# tester-2.net
KiCad netlist of a schematic drawn in EAGLE
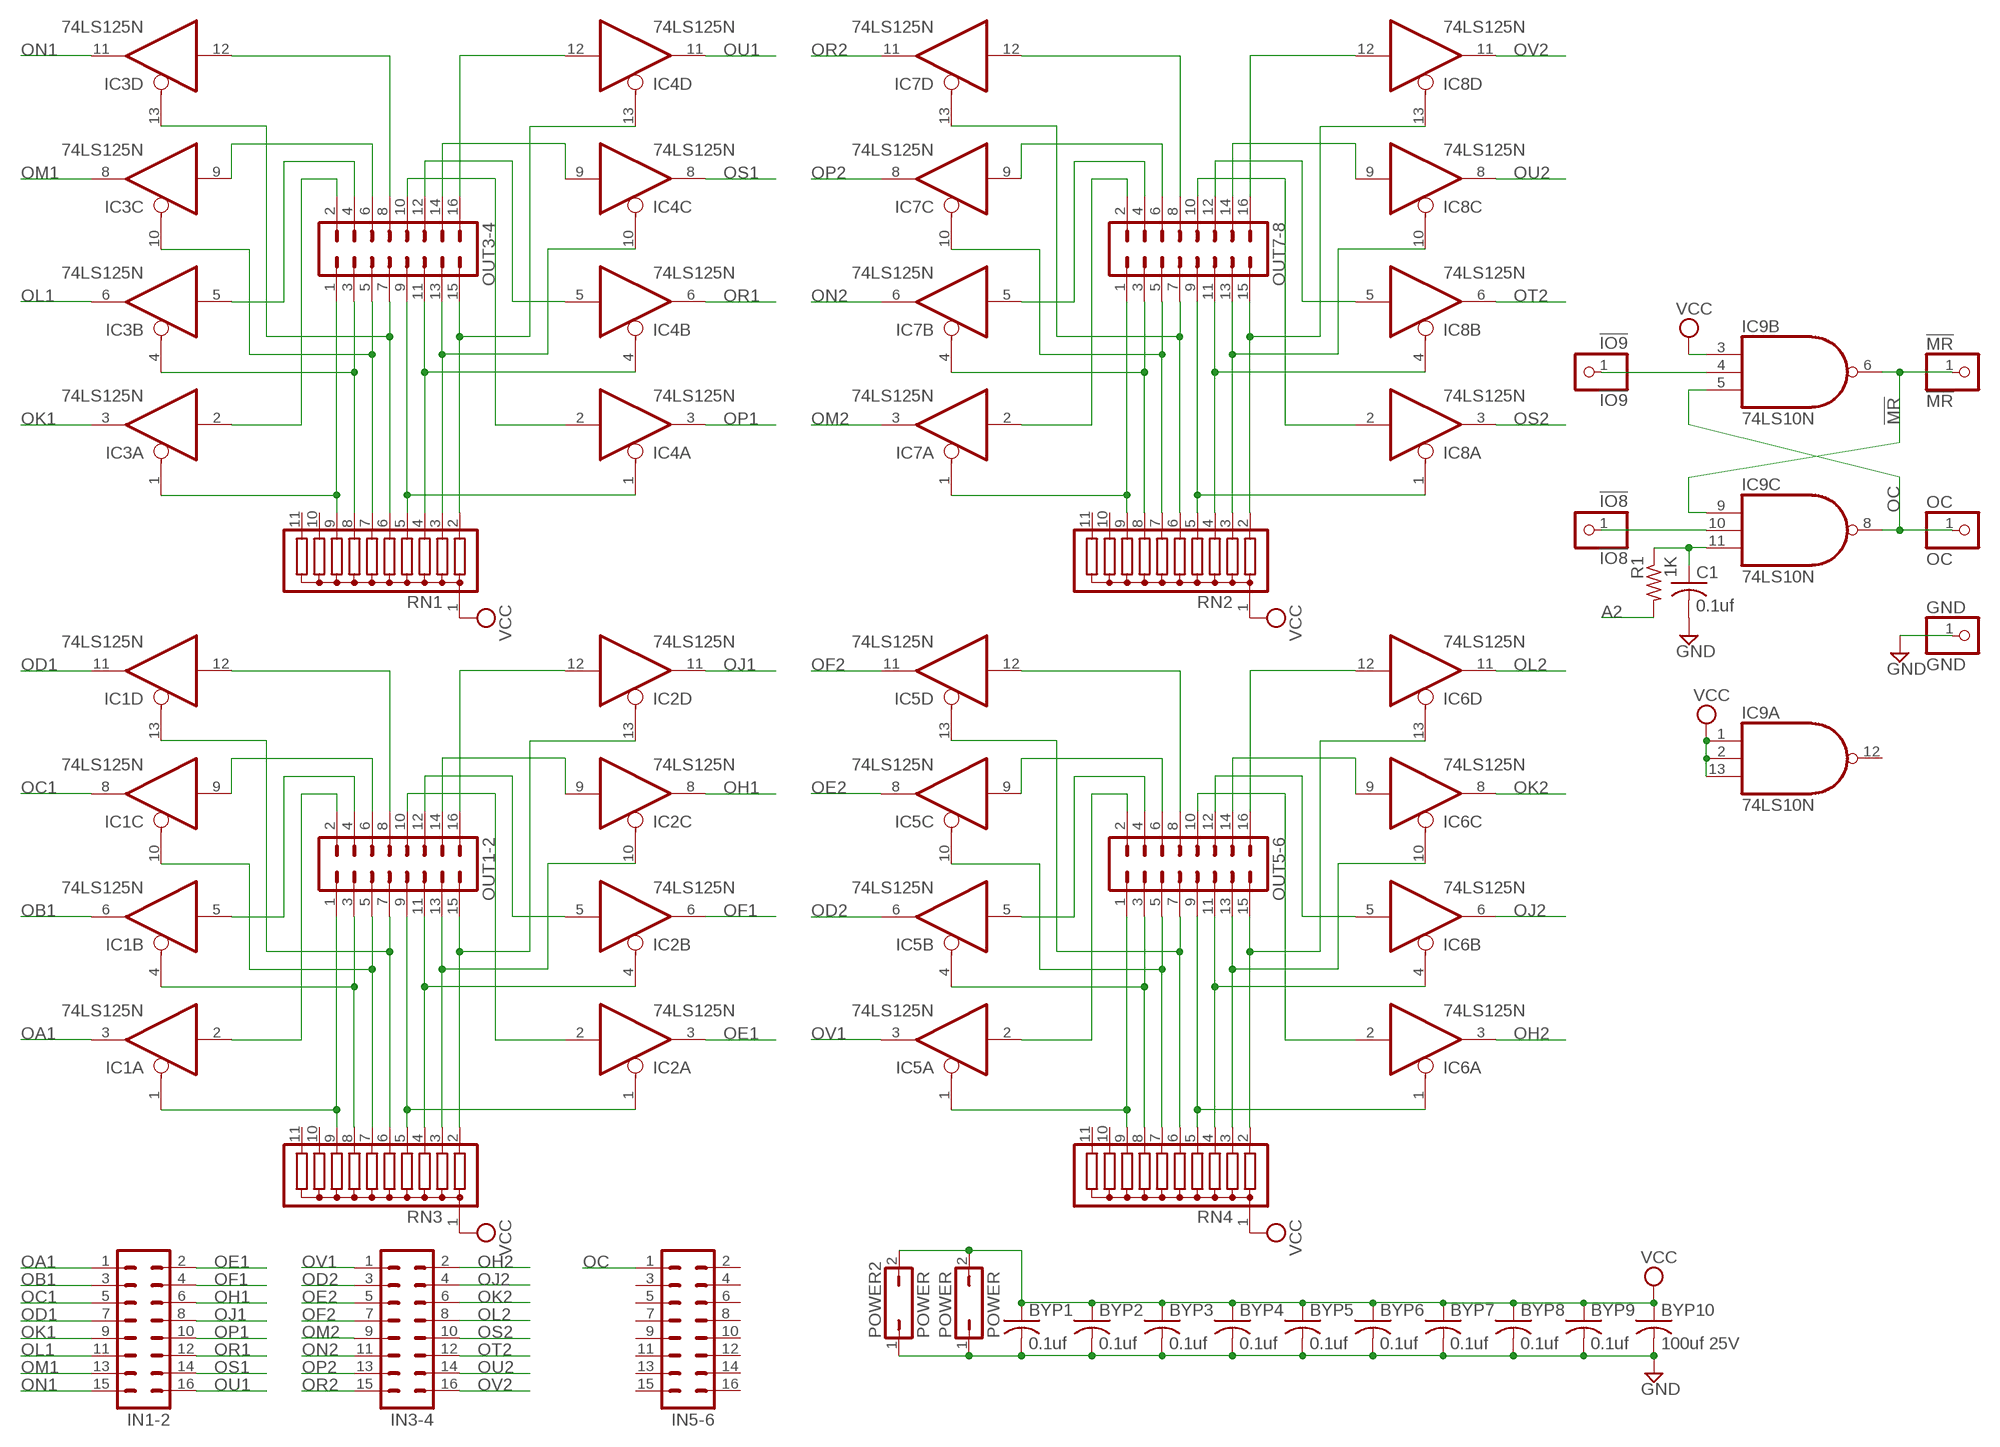
[diagram p0: schematic, sheet 1]
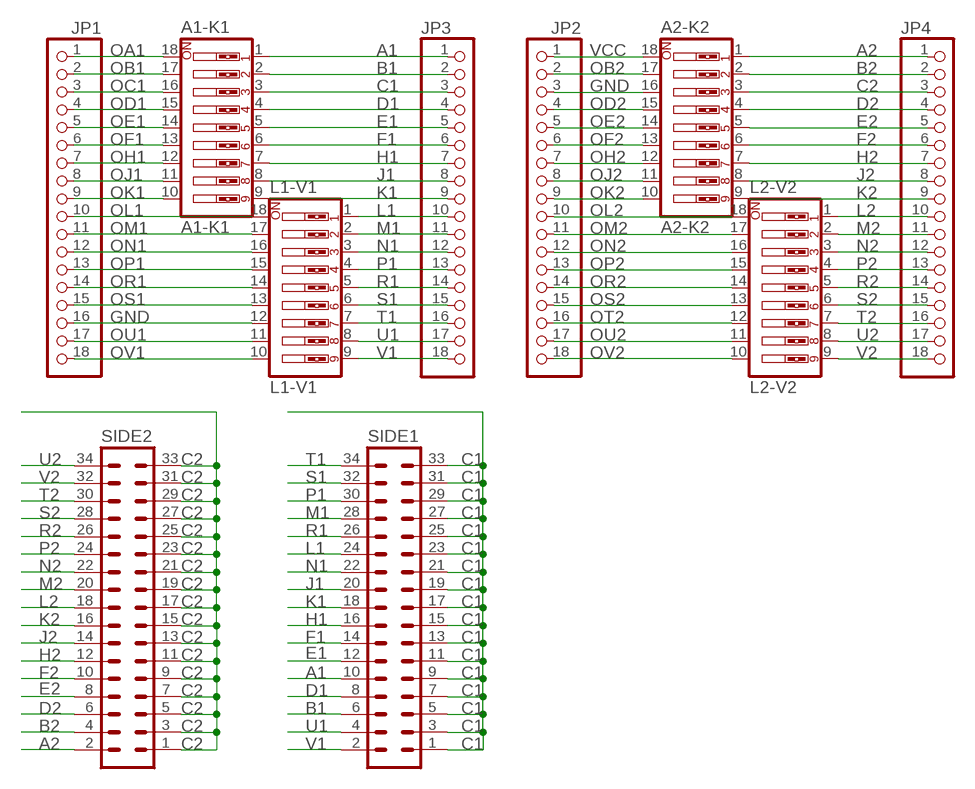
[diagram p1: schematic, sheet 2]

(export (version "E")
  (design (tool "Eeschema 10.0.6"))
  (components
    (comp (ref "A1-K1")
      (value "A1-K1")
      (footprint "eagle-import:EDG-09")
      (libsource (lib "eagle-import") (part "SW_DIP-9"))
    )
    (comp (ref "A2-K2")
      (value "A2-K2")
      (footprint "eagle-import:EDG-09")
      (libsource (lib "eagle-import") (part "SW_DIP-9"))
    )
    (comp (ref "JP1")
      (value "PINHD-1X18")
      (footprint "eagle-import:1X18")
      (libsource (lib "eagle-import") (part "PINHD-1X18"))
    )
    (comp (ref "JP2")
      (value "PINHD-1X18")
      (footprint "eagle-import:1X18")
      (libsource (lib "eagle-import") (part "PINHD-1X18"))
    )
    (comp (ref "JP3")
      (value "PINHD-1X18")
      (footprint "eagle-import:1X18")
      (libsource (lib "eagle-import") (part "PINHD-1X18"))
    )
    (comp (ref "JP4")
      (value "PINHD-1X18")
      (footprint "eagle-import:1X18")
      (libsource (lib "eagle-import") (part "PINHD-1X18"))
    )
    (comp (ref "L1-V1")
      (value "L1-V1")
      (footprint "eagle-import:EDG-09")
      (libsource (lib "eagle-import") (part "SW_DIP-9"))
    )
    (comp (ref "L2-V2")
      (value "L2-V2")
      (footprint "eagle-import:EDG-09")
      (libsource (lib "eagle-import") (part "SW_DIP-9"))
    )
    (comp (ref "SIDE1")
      (value "MA17-2")
      (footprint "eagle-import:MA17-2")
      (libsource (lib "eagle-import") (part "MA17-2"))
    )
    (comp (ref "SIDE2")
      (value "MA17-2")
      (footprint "eagle-import:MA17-2")
      (libsource (lib "eagle-import") (part "MA17-2"))
    )
    (comp (ref "!IO8")
      (value "!IO8")
      (footprint "eagle-import:1X01")
      (libsource (lib "eagle-import") (part "PINHD-1X1"))
    )
    (comp (ref "!IO9")
      (value "!IO9")
      (footprint "eagle-import:1X01")
      (libsource (lib "eagle-import") (part "PINHD-1X1"))
    )
    (comp (ref "!MR")
      (value "!MR")
      (footprint "eagle-import:1X01")
      (libsource (lib "eagle-import") (part "PINHD-1X1"))
    )
    (comp (ref "BYP1")
      (value "0.1uf")
      (footprint "eagle-import:C050-025X075")
      (libsource (lib "eagle-import") (part "C-US050-025X075"))
    )
    (comp (ref "BYP2")
      (value "0.1uf")
      (footprint "eagle-import:C050-025X075")
      (libsource (lib "eagle-import") (part "C-US050-025X075"))
    )
    (comp (ref "BYP3")
      (value "0.1uf")
      (footprint "eagle-import:C050-025X075")
      (libsource (lib "eagle-import") (part "C-US050-025X075"))
    )
    (comp (ref "BYP4")
      (value "0.1uf")
      (footprint "eagle-import:C050-025X075")
      (libsource (lib "eagle-import") (part "C-US050-025X075"))
    )
    (comp (ref "BYP5")
      (value "0.1uf")
      (footprint "eagle-import:C050-025X075")
      (libsource (lib "eagle-import") (part "C-US050-025X075"))
    )
    (comp (ref "BYP6")
      (value "0.1uf")
      (footprint "eagle-import:C050-025X075")
      (libsource (lib "eagle-import") (part "C-US050-025X075"))
    )
    (comp (ref "BYP7")
      (value "0.1uf")
      (footprint "eagle-import:C050-025X075")
      (libsource (lib "eagle-import") (part "C-US050-025X075"))
    )
    (comp (ref "BYP8")
      (value "0.1uf")
      (footprint "eagle-import:C050-025X075")
      (libsource (lib "eagle-import") (part "C-US050-025X075"))
    )
    (comp (ref "BYP9")
      (value "0.1uf")
      (footprint "eagle-import:C050-025X075")
      (libsource (lib "eagle-import") (part "C-US050-025X075"))
    )
    (comp (ref "BYP10")
      (value "100uf 25V")
      (footprint "eagle-import:C150-064X183")
      (libsource (lib "eagle-import") (part "C-US150-064X183"))
    )
    (comp (ref "C1")
      (value "0.1uf")
      (footprint "eagle-import:C050-025X075")
      (libsource (lib "eagle-import") (part "C-US050-025X075"))
    )
    (comp (ref "GND")
      (value "GND")
      (footprint "eagle-import:1X01")
      (libsource (lib "eagle-import") (part "PINHD-1X1"))
    )
    (comp (ref "IC1")
      (value "74LS125N")
      (footprint "eagle-import:DIL14")
      (libsource (lib "eagle-import") (part "74125NLS"))
    )
    (comp (ref "IC2")
      (value "74LS125N")
      (footprint "eagle-import:DIL14")
      (libsource (lib "eagle-import") (part "74125NLS"))
    )
    (comp (ref "IC3")
      (value "74LS125N")
      (footprint "eagle-import:DIL14")
      (libsource (lib "eagle-import") (part "74125NLS"))
    )
    (comp (ref "IC4")
      (value "74LS125N")
      (footprint "eagle-import:DIL14")
      (libsource (lib "eagle-import") (part "74125NLS"))
    )
    (comp (ref "IC5")
      (value "74LS125N")
      (footprint "eagle-import:DIL14")
      (libsource (lib "eagle-import") (part "74125NLS"))
    )
    (comp (ref "IC6")
      (value "74LS125N")
      (footprint "eagle-import:DIL14")
      (libsource (lib "eagle-import") (part "74125NLS"))
    )
    (comp (ref "IC7")
      (value "74LS125N")
      (footprint "eagle-import:DIL14")
      (libsource (lib "eagle-import") (part "74125NLS"))
    )
    (comp (ref "IC8")
      (value "74LS125N")
      (footprint "eagle-import:DIL14")
      (libsource (lib "eagle-import") (part "74125NLS"))
    )
    (comp (ref "IC9")
      (value "74LS10N")
      (footprint "eagle-import:DIL14")
      (libsource (lib "eagle-import") (part "7410NLS"))
    )
    (comp (ref "IN1-2")
      (value "MA08-2")
      (footprint "eagle-import:MA08-2")
      (libsource (lib "eagle-import") (part "MA08-2"))
    )
    (comp (ref "IN3-4")
      (value "MA08-2")
      (footprint "eagle-import:MA08-2")
      (libsource (lib "eagle-import") (part "MA08-2"))
    )
    (comp (ref "IN5-6")
      (value "MA08-2")
      (footprint "eagle-import:MA08-2")
      (libsource (lib "eagle-import") (part "MA08-2"))
    )
    (comp (ref "OC")
      (value "OC")
      (footprint "eagle-import:1X01")
      (libsource (lib "eagle-import") (part "PINHD-1X1"))
    )
    (comp (ref "OUT1-2")
      (value "MA08-2")
      (footprint "eagle-import:MA08-2")
      (libsource (lib "eagle-import") (part "MA08-2"))
    )
    (comp (ref "OUT3-4")
      (value "MA08-2")
      (footprint "eagle-import:MA08-2")
      (libsource (lib "eagle-import") (part "MA08-2"))
    )
    (comp (ref "OUT5-6")
      (value "MA08-2")
      (footprint "eagle-import:MA08-2")
      (libsource (lib "eagle-import") (part "MA08-2"))
    )
    (comp (ref "OUT7-8")
      (value "MA08-2")
      (footprint "eagle-import:MA08-2")
      (libsource (lib "eagle-import") (part "MA08-2"))
    )
    (comp (ref "POWER")
      (value "POWER")
      (footprint "eagle-import:JP1")
      (libsource (lib "eagle-import") (part "JP1Q"))
    )
    (comp (ref "POWER2")
      (value "POWER")
      (footprint "eagle-import:JP1")
      (libsource (lib "eagle-import") (part "JP1Q"))
    )
    (comp (ref "R1")
      (value "1K")
      (footprint "eagle-import:0207_10")
      (libsource (lib "eagle-import") (part "R-US_0207/10"))
    )
    (comp (ref "RN1")
      (value "G10R")
      (footprint "eagle-import:SIL11")
      (libsource (lib "eagle-import") (part "G10R"))
    )
    (comp (ref "RN2")
      (value "G10R")
      (footprint "eagle-import:SIL11")
      (libsource (lib "eagle-import") (part "G10R"))
    )
    (comp (ref "RN3")
      (value "G10R")
      (footprint "eagle-import:SIL11")
      (libsource (lib "eagle-import") (part "G10R"))
    )
    (comp (ref "RN4")
      (value "G10R")
      (footprint "eagle-import:SIL11")
      (libsource (lib "eagle-import") (part "G10R"))
    )
  )
  (nets
    (net (code "1") (name "A1") (class "Default")
      (node (ref "A1-K1") (pin "1") (pinfunction "1_1") (pintype "passive"))
      (node (ref "JP3") (pin "1") (pinfunction "1_1") (pintype "passive"))
      (node (ref "SIDE1") (pin "10") (pinfunction "10_10") (pintype "passive"))
    )
    (net (code "2") (name "A2") (class "Default")
      (node (ref "A2-K2") (pin "1") (pinfunction "1_1") (pintype "passive"))
      (node (ref "JP4") (pin "1") (pinfunction "1_1") (pintype "passive"))
      (node (ref "R1") (pin "2") (pinfunction "2_2") (pintype "passive"))
      (node (ref "SIDE2") (pin "2") (pinfunction "2_2") (pintype "passive"))
    )
    (net (code "3") (name "B1") (class "Default")
      (node (ref "A1-K1") (pin "2") (pinfunction "2_2") (pintype "passive"))
      (node (ref "JP3") (pin "2") (pinfunction "2_2") (pintype "passive"))
      (node (ref "SIDE1") (pin "6") (pinfunction "6_6") (pintype "passive"))
    )
    (net (code "4") (name "B2") (class "Default")
      (node (ref "A2-K2") (pin "2") (pinfunction "2_2") (pintype "passive"))
      (node (ref "JP4") (pin "2") (pinfunction "2_2") (pintype "passive"))
      (node (ref "SIDE2") (pin "4") (pinfunction "4_4") (pintype "passive"))
    )
    (net (code "5") (name "C1") (class "Default")
      (node (ref "A1-K1") (pin "3") (pinfunction "3_3") (pintype "passive"))
      (node (ref "JP3") (pin "3") (pinfunction "3_3") (pintype "passive"))
      (node (ref "SIDE1") (pin "1") (pinfunction "1_1") (pintype "passive"))
      (node (ref "SIDE1") (pin "11") (pinfunction "11_11") (pintype "passive"))
      (node (ref "SIDE1") (pin "13") (pinfunction "13_13") (pintype "passive"))
      (node (ref "SIDE1") (pin "15") (pinfunction "15_15") (pintype "passive"))
      (node (ref "SIDE1") (pin "17") (pinfunction "17_17") (pintype "passive"))
      (node (ref "SIDE1") (pin "19") (pinfunction "19_19") (pintype "passive"))
      (node (ref "SIDE1") (pin "21") (pinfunction "21_21") (pintype "passive"))
      (node (ref "SIDE1") (pin "23") (pinfunction "23_23") (pintype "passive"))
      (node (ref "SIDE1") (pin "25") (pinfunction "25_25") (pintype "passive"))
      (node (ref "SIDE1") (pin "27") (pinfunction "27_27") (pintype "passive"))
      (node (ref "SIDE1") (pin "29") (pinfunction "29_29") (pintype "passive"))
      (node (ref "SIDE1") (pin "3") (pinfunction "3_3") (pintype "passive"))
      (node (ref "SIDE1") (pin "31") (pinfunction "31_31") (pintype "passive"))
      (node (ref "SIDE1") (pin "33") (pinfunction "33_33") (pintype "passive"))
      (node (ref "SIDE1") (pin "5") (pinfunction "5_5") (pintype "passive"))
      (node (ref "SIDE1") (pin "7") (pinfunction "7_7") (pintype "passive"))
      (node (ref "SIDE1") (pin "9") (pinfunction "9_9") (pintype "passive"))
    )
    (net (code "6") (name "C2") (class "Default")
      (node (ref "A2-K2") (pin "3") (pinfunction "3_3") (pintype "passive"))
      (node (ref "JP4") (pin "3") (pinfunction "3_3") (pintype "passive"))
      (node (ref "SIDE2") (pin "1") (pinfunction "1_1") (pintype "passive"))
      (node (ref "SIDE2") (pin "11") (pinfunction "11_11") (pintype "passive"))
      (node (ref "SIDE2") (pin "13") (pinfunction "13_13") (pintype "passive"))
      (node (ref "SIDE2") (pin "15") (pinfunction "15_15") (pintype "passive"))
      (node (ref "SIDE2") (pin "17") (pinfunction "17_17") (pintype "passive"))
      (node (ref "SIDE2") (pin "19") (pinfunction "19_19") (pintype "passive"))
      (node (ref "SIDE2") (pin "21") (pinfunction "21_21") (pintype "passive"))
      (node (ref "SIDE2") (pin "23") (pinfunction "23_23") (pintype "passive"))
      (node (ref "SIDE2") (pin "25") (pinfunction "25_25") (pintype "passive"))
      (node (ref "SIDE2") (pin "27") (pinfunction "27_27") (pintype "passive"))
      (node (ref "SIDE2") (pin "29") (pinfunction "29_29") (pintype "passive"))
      (node (ref "SIDE2") (pin "3") (pinfunction "3_3") (pintype "passive"))
      (node (ref "SIDE2") (pin "31") (pinfunction "31_31") (pintype "passive"))
      (node (ref "SIDE2") (pin "33") (pinfunction "33_33") (pintype "passive"))
      (node (ref "SIDE2") (pin "5") (pinfunction "5_5") (pintype "passive"))
      (node (ref "SIDE2") (pin "7") (pinfunction "7_7") (pintype "passive"))
      (node (ref "SIDE2") (pin "9") (pinfunction "9_9") (pintype "passive"))
    )
    (net (code "7") (name "D1") (class "Default")
      (node (ref "A1-K1") (pin "4") (pinfunction "4_4") (pintype "passive"))
      (node (ref "JP3") (pin "4") (pinfunction "4_4") (pintype "passive"))
      (node (ref "SIDE1") (pin "8") (pinfunction "8_8") (pintype "passive"))
    )
    (net (code "8") (name "D2") (class "Default")
      (node (ref "A2-K2") (pin "4") (pinfunction "4_4") (pintype "passive"))
      (node (ref "JP4") (pin "4") (pinfunction "4_4") (pintype "passive"))
      (node (ref "SIDE2") (pin "6") (pinfunction "6_6") (pintype "passive"))
    )
    (net (code "9") (name "E1") (class "Default")
      (node (ref "A1-K1") (pin "5") (pinfunction "5_5") (pintype "passive"))
      (node (ref "JP3") (pin "5") (pinfunction "5_5") (pintype "passive"))
      (node (ref "SIDE1") (pin "12") (pinfunction "12_12") (pintype "passive"))
    )
    (net (code "10") (name "E2") (class "Default")
      (node (ref "A2-K2") (pin "5") (pinfunction "5_5") (pintype "passive"))
      (node (ref "JP4") (pin "5") (pinfunction "5_5") (pintype "passive"))
      (node (ref "SIDE2") (pin "8") (pinfunction "8_8") (pintype "passive"))
    )
    (net (code "11") (name "F1") (class "Default")
      (node (ref "A1-K1") (pin "6") (pinfunction "6_6") (pintype "passive"))
      (node (ref "JP3") (pin "6") (pinfunction "6_6") (pintype "passive"))
      (node (ref "SIDE1") (pin "14") (pinfunction "14_14") (pintype "passive"))
    )
    (net (code "12") (name "F2") (class "Default")
      (node (ref "A2-K2") (pin "6") (pinfunction "6_6") (pintype "passive"))
      (node (ref "JP4") (pin "6") (pinfunction "6_6") (pintype "passive"))
      (node (ref "SIDE2") (pin "10") (pinfunction "10_10") (pintype "passive"))
    )
    (net (code "13") (name "GND") (class "Default")
      (node (ref "A2-K2") (pin "16") (pinfunction "16_16") (pintype "passive"))
      (node (ref "BYP1") (pin "2") (pinfunction "2_2") (pintype "passive"))
      (node (ref "BYP10") (pin "2") (pinfunction "2_2") (pintype "passive"))
      (node (ref "BYP2") (pin "2") (pinfunction "2_2") (pintype "passive"))
      (node (ref "BYP3") (pin "2") (pinfunction "2_2") (pintype "passive"))
      (node (ref "BYP4") (pin "2") (pinfunction "2_2") (pintype "passive"))
      (node (ref "BYP5") (pin "2") (pinfunction "2_2") (pintype "passive"))
      (node (ref "BYP6") (pin "2") (pinfunction "2_2") (pintype "passive"))
      (node (ref "BYP7") (pin "2") (pinfunction "2_2") (pintype "passive"))
      (node (ref "BYP8") (pin "2") (pinfunction "2_2") (pintype "passive"))
      (node (ref "BYP9") (pin "2") (pinfunction "2_2") (pintype "passive"))
      (node (ref "C1") (pin "2") (pinfunction "2_2") (pintype "passive"))
      (node (ref "GND") (pin "1") (pinfunction "1_1") (pintype "passive"))
      (node (ref "JP1") (pin "16") (pinfunction "16_16") (pintype "passive"))
      (node (ref "JP2") (pin "3") (pinfunction "3_3") (pintype "passive"))
      (node (ref "L1-V1") (pin "12") (pinfunction "12_12") (pintype "passive"))
      (node (ref "POWER") (pin "1") (pinfunction "1_1") (pintype "passive"))
      (node (ref "POWER2") (pin "1") (pinfunction "1_1") (pintype "passive"))
    )
    (net (code "14") (name "H1") (class "Default")
      (node (ref "A1-K1") (pin "7") (pinfunction "7_7") (pintype "passive"))
      (node (ref "JP3") (pin "7") (pinfunction "7_7") (pintype "passive"))
      (node (ref "SIDE1") (pin "16") (pinfunction "16_16") (pintype "passive"))
    )
    (net (code "15") (name "H2") (class "Default")
      (node (ref "A2-K2") (pin "7") (pinfunction "7_7") (pintype "passive"))
      (node (ref "JP4") (pin "7") (pinfunction "7_7") (pintype "passive"))
      (node (ref "SIDE2") (pin "12") (pinfunction "12_12") (pintype "passive"))
    )
    (net (code "16") (name "J1") (class "Default")
      (node (ref "A1-K1") (pin "8") (pinfunction "8_8") (pintype "passive"))
      (node (ref "JP3") (pin "8") (pinfunction "8_8") (pintype "passive"))
      (node (ref "SIDE1") (pin "20") (pinfunction "20_20") (pintype "passive"))
    )
    (net (code "17") (name "J2") (class "Default")
      (node (ref "A2-K2") (pin "8") (pinfunction "8_8") (pintype "passive"))
      (node (ref "JP4") (pin "8") (pinfunction "8_8") (pintype "passive"))
      (node (ref "SIDE2") (pin "14") (pinfunction "14_14") (pintype "passive"))
    )
    (net (code "18") (name "K1") (class "Default")
      (node (ref "A1-K1") (pin "9") (pinfunction "9_9") (pintype "passive"))
      (node (ref "JP3") (pin "9") (pinfunction "9_9") (pintype "passive"))
      (node (ref "SIDE1") (pin "18") (pinfunction "18_18") (pintype "passive"))
    )
    (net (code "19") (name "K2") (class "Default")
      (node (ref "A2-K2") (pin "9") (pinfunction "9_9") (pintype "passive"))
      (node (ref "JP4") (pin "9") (pinfunction "9_9") (pintype "passive"))
      (node (ref "SIDE2") (pin "16") (pinfunction "16_16") (pintype "passive"))
    )
    (net (code "20") (name "L1") (class "Default")
      (node (ref "JP3") (pin "10") (pinfunction "10_10") (pintype "passive"))
      (node (ref "L1-V1") (pin "1") (pinfunction "1_1") (pintype "passive"))
      (node (ref "SIDE1") (pin "24") (pinfunction "24_24") (pintype "passive"))
    )
    (net (code "21") (name "L2") (class "Default")
      (node (ref "JP4") (pin "10") (pinfunction "10_10") (pintype "passive"))
      (node (ref "L2-V2") (pin "1") (pinfunction "1_1") (pintype "passive"))
      (node (ref "SIDE2") (pin "18") (pinfunction "18_18") (pintype "passive"))
    )
    (net (code "22") (name "M1") (class "Default")
      (node (ref "JP3") (pin "11") (pinfunction "11_11") (pintype "passive"))
      (node (ref "L1-V1") (pin "2") (pinfunction "2_2") (pintype "passive"))
      (node (ref "SIDE1") (pin "28") (pinfunction "28_28") (pintype "passive"))
    )
    (net (code "23") (name "M2") (class "Default")
      (node (ref "JP4") (pin "11") (pinfunction "11_11") (pintype "passive"))
      (node (ref "L2-V2") (pin "2") (pinfunction "2_2") (pintype "passive"))
      (node (ref "SIDE2") (pin "20") (pinfunction "20_20") (pintype "passive"))
    )
    (net (code "24") (name "N1") (class "Default")
      (node (ref "JP3") (pin "12") (pinfunction "12_12") (pintype "passive"))
      (node (ref "L1-V1") (pin "3") (pinfunction "3_3") (pintype "passive"))
      (node (ref "SIDE1") (pin "22") (pinfunction "22_22") (pintype "passive"))
    )
    (net (code "25") (name "N2") (class "Default")
      (node (ref "JP4") (pin "12") (pinfunction "12_12") (pintype "passive"))
      (node (ref "L2-V2") (pin "3") (pinfunction "3_3") (pintype "passive"))
      (node (ref "SIDE2") (pin "22") (pinfunction "22_22") (pintype "passive"))
    )
    (net (code "26") (name "Net-(IC1A-I)") (class "Default")
      (node (ref "IC1") (pin "2") (pinfunction "I_2") (pintype "input"))
      (node (ref "OUT1-2") (pin "2") (pinfunction "2_2") (pintype "passive"))
    )
    (net (code "27") (name "Net-(IC1A-OE)") (class "Default")
      (node (ref "IC1") (pin "1") (pinfunction "OE_1") (pintype "input"))
      (node (ref "OUT1-2") (pin "1") (pinfunction "1_1") (pintype "passive"))
      (node (ref "RN3") (pin "9") (pinfunction "9_9") (pintype "passive"))
    )
    (net (code "28") (name "Net-(IC1B-I)") (class "Default")
      (node (ref "IC1") (pin "5") (pinfunction "I_5") (pintype "input"))
      (node (ref "OUT1-2") (pin "4") (pinfunction "4_4") (pintype "passive"))
    )
    (net (code "29") (name "Net-(IC1B-OE)") (class "Default")
      (node (ref "IC1") (pin "4") (pinfunction "OE_4") (pintype "input"))
      (node (ref "OUT1-2") (pin "3") (pinfunction "3_3") (pintype "passive"))
      (node (ref "RN3") (pin "8") (pinfunction "8_8") (pintype "passive"))
    )
    (net (code "30") (name "Net-(IC1C-I)") (class "Default")
      (node (ref "IC1") (pin "9") (pinfunction "I_9") (pintype "input"))
      (node (ref "OUT1-2") (pin "6") (pinfunction "6_6") (pintype "passive"))
    )
    (net (code "31") (name "Net-(IC1C-OE)") (class "Default")
      (node (ref "IC1") (pin "10") (pinfunction "OE_10") (pintype "input"))
      (node (ref "OUT1-2") (pin "5") (pinfunction "5_5") (pintype "passive"))
      (node (ref "RN3") (pin "7") (pinfunction "7_7") (pintype "passive"))
    )
    (net (code "32") (name "Net-(IC1D-I)") (class "Default")
      (node (ref "IC1") (pin "12") (pinfunction "I_12") (pintype "input"))
      (node (ref "OUT1-2") (pin "8") (pinfunction "8_8") (pintype "passive"))
    )
    (net (code "33") (name "Net-(IC1D-OE)") (class "Default")
      (node (ref "IC1") (pin "13") (pinfunction "OE_13") (pintype "input"))
      (node (ref "OUT1-2") (pin "7") (pinfunction "7_7") (pintype "passive"))
      (node (ref "RN3") (pin "6") (pinfunction "6_6") (pintype "passive"))
    )
    (net (code "34") (name "Net-(IC2A-I)") (class "Default")
      (node (ref "IC2") (pin "2") (pinfunction "I_2") (pintype "input"))
      (node (ref "OUT1-2") (pin "10") (pinfunction "10_10") (pintype "passive"))
    )
    (net (code "35") (name "Net-(IC2A-OE)") (class "Default")
      (node (ref "IC2") (pin "1") (pinfunction "OE_1") (pintype "input"))
      (node (ref "OUT1-2") (pin "9") (pinfunction "9_9") (pintype "passive"))
      (node (ref "RN3") (pin "5") (pinfunction "5_5") (pintype "passive"))
    )
    (net (code "36") (name "Net-(IC2B-I)") (class "Default")
      (node (ref "IC2") (pin "5") (pinfunction "I_5") (pintype "input"))
      (node (ref "OUT1-2") (pin "12") (pinfunction "12_12") (pintype "passive"))
    )
    (net (code "37") (name "Net-(IC2B-OE)") (class "Default")
      (node (ref "IC2") (pin "4") (pinfunction "OE_4") (pintype "input"))
      (node (ref "OUT1-2") (pin "11") (pinfunction "11_11") (pintype "passive"))
      (node (ref "RN3") (pin "4") (pinfunction "4_4") (pintype "passive"))
    )
    (net (code "38") (name "Net-(IC2C-I)") (class "Default")
      (node (ref "IC2") (pin "9") (pinfunction "I_9") (pintype "input"))
      (node (ref "OUT1-2") (pin "14") (pinfunction "14_14") (pintype "passive"))
    )
    (net (code "39") (name "Net-(IC2C-OE)") (class "Default")
      (node (ref "IC2") (pin "10") (pinfunction "OE_10") (pintype "input"))
      (node (ref "OUT1-2") (pin "13") (pinfunction "13_13") (pintype "passive"))
      (node (ref "RN3") (pin "3") (pinfunction "3_3") (pintype "passive"))
    )
    (net (code "40") (name "Net-(IC2D-I)") (class "Default")
      (node (ref "IC2") (pin "12") (pinfunction "I_12") (pintype "input"))
      (node (ref "OUT1-2") (pin "16") (pinfunction "16_16") (pintype "passive"))
    )
    (net (code "41") (name "Net-(IC2D-OE)") (class "Default")
      (node (ref "IC2") (pin "13") (pinfunction "OE_13") (pintype "input"))
      (node (ref "OUT1-2") (pin "15") (pinfunction "15_15") (pintype "passive"))
      (node (ref "RN3") (pin "2") (pinfunction "2_2") (pintype "passive"))
    )
    (net (code "42") (name "Net-(IC3A-I)") (class "Default")
      (node (ref "IC3") (pin "2") (pinfunction "I_2") (pintype "input"))
      (node (ref "OUT3-4") (pin "2") (pinfunction "2_2") (pintype "passive"))
    )
    (net (code "43") (name "Net-(IC3A-OE)") (class "Default")
      (node (ref "IC3") (pin "1") (pinfunction "OE_1") (pintype "input"))
      (node (ref "OUT3-4") (pin "1") (pinfunction "1_1") (pintype "passive"))
      (node (ref "RN1") (pin "9") (pinfunction "9_9") (pintype "passive"))
    )
    (net (code "44") (name "Net-(IC3B-I)") (class "Default")
      (node (ref "IC3") (pin "5") (pinfunction "I_5") (pintype "input"))
      (node (ref "OUT3-4") (pin "4") (pinfunction "4_4") (pintype "passive"))
    )
    (net (code "45") (name "Net-(IC3B-OE)") (class "Default")
      (node (ref "IC3") (pin "4") (pinfunction "OE_4") (pintype "input"))
      (node (ref "OUT3-4") (pin "3") (pinfunction "3_3") (pintype "passive"))
      (node (ref "RN1") (pin "8") (pinfunction "8_8") (pintype "passive"))
    )
    (net (code "46") (name "Net-(IC3C-I)") (class "Default")
      (node (ref "IC3") (pin "9") (pinfunction "I_9") (pintype "input"))
      (node (ref "OUT3-4") (pin "6") (pinfunction "6_6") (pintype "passive"))
    )
    (net (code "47") (name "Net-(IC3C-OE)") (class "Default")
      (node (ref "IC3") (pin "10") (pinfunction "OE_10") (pintype "input"))
      (node (ref "OUT3-4") (pin "5") (pinfunction "5_5") (pintype "passive"))
      (node (ref "RN1") (pin "7") (pinfunction "7_7") (pintype "passive"))
    )
    (net (code "48") (name "Net-(IC3D-I)") (class "Default")
      (node (ref "IC3") (pin "12") (pinfunction "I_12") (pintype "input"))
      (node (ref "OUT3-4") (pin "8") (pinfunction "8_8") (pintype "passive"))
    )
    (net (code "49") (name "Net-(IC3D-OE)") (class "Default")
      (node (ref "IC3") (pin "13") (pinfunction "OE_13") (pintype "input"))
      (node (ref "OUT3-4") (pin "7") (pinfunction "7_7") (pintype "passive"))
      (node (ref "RN1") (pin "6") (pinfunction "6_6") (pintype "passive"))
    )
    (net (code "50") (name "Net-(IC4A-I)") (class "Default")
      (node (ref "IC4") (pin "2") (pinfunction "I_2") (pintype "input"))
      (node (ref "OUT3-4") (pin "10") (pinfunction "10_10") (pintype "passive"))
    )
    (net (code "51") (name "Net-(IC4A-OE)") (class "Default")
      (node (ref "IC4") (pin "1") (pinfunction "OE_1") (pintype "input"))
      (node (ref "OUT3-4") (pin "9") (pinfunction "9_9") (pintype "passive"))
      (node (ref "RN1") (pin "5") (pinfunction "5_5") (pintype "passive"))
    )
    (net (code "52") (name "Net-(IC4B-I)") (class "Default")
      (node (ref "IC4") (pin "5") (pinfunction "I_5") (pintype "input"))
      (node (ref "OUT3-4") (pin "12") (pinfunction "12_12") (pintype "passive"))
    )
    (net (code "53") (name "Net-(IC4B-OE)") (class "Default")
      (node (ref "IC4") (pin "4") (pinfunction "OE_4") (pintype "input"))
      (node (ref "OUT3-4") (pin "11") (pinfunction "11_11") (pintype "passive"))
      (node (ref "RN1") (pin "4") (pinfunction "4_4") (pintype "passive"))
    )
    (net (code "54") (name "Net-(IC4C-I)") (class "Default")
      (node (ref "IC4") (pin "9") (pinfunction "I_9") (pintype "input"))
      (node (ref "OUT3-4") (pin "14") (pinfunction "14_14") (pintype "passive"))
    )
    (net (code "55") (name "Net-(IC4C-OE)") (class "Default")
      (node (ref "IC4") (pin "10") (pinfunction "OE_10") (pintype "input"))
      (node (ref "OUT3-4") (pin "13") (pinfunction "13_13") (pintype "passive"))
      (node (ref "RN1") (pin "3") (pinfunction "3_3") (pintype "passive"))
    )
    (net (code "56") (name "Net-(IC4D-I)") (class "Default")
      (node (ref "IC4") (pin "12") (pinfunction "I_12") (pintype "input"))
      (node (ref "OUT3-4") (pin "16") (pinfunction "16_16") (pintype "passive"))
    )
    (net (code "57") (name "Net-(IC4D-OE)") (class "Default")
      (node (ref "IC4") (pin "13") (pinfunction "OE_13") (pintype "input"))
      (node (ref "OUT3-4") (pin "15") (pinfunction "15_15") (pintype "passive"))
      (node (ref "RN1") (pin "2") (pinfunction "2_2") (pintype "passive"))
    )
    (net (code "58") (name "Net-(IC5A-I)") (class "Default")
      (node (ref "IC5") (pin "2") (pinfunction "I_2") (pintype "input"))
      (node (ref "OUT5-6") (pin "2") (pinfunction "2_2") (pintype "passive"))
    )
    (net (code "59") (name "Net-(IC5A-OE)") (class "Default")
      (node (ref "IC5") (pin "1") (pinfunction "OE_1") (pintype "input"))
      (node (ref "OUT5-6") (pin "1") (pinfunction "1_1") (pintype "passive"))
      (node (ref "RN4") (pin "9") (pinfunction "9_9") (pintype "passive"))
    )
    (net (code "60") (name "Net-(IC5B-I)") (class "Default")
      (node (ref "IC5") (pin "5") (pinfunction "I_5") (pintype "input"))
      (node (ref "OUT5-6") (pin "4") (pinfunction "4_4") (pintype "passive"))
    )
    (net (code "61") (name "Net-(IC5B-OE)") (class "Default")
      (node (ref "IC5") (pin "4") (pinfunction "OE_4") (pintype "input"))
      (node (ref "OUT5-6") (pin "3") (pinfunction "3_3") (pintype "passive"))
      (node (ref "RN4") (pin "8") (pinfunction "8_8") (pintype "passive"))
    )
    (net (code "62") (name "Net-(IC5C-I)") (class "Default")
      (node (ref "IC5") (pin "9") (pinfunction "I_9") (pintype "input"))
      (node (ref "OUT5-6") (pin "6") (pinfunction "6_6") (pintype "passive"))
    )
    (net (code "63") (name "Net-(IC5C-OE)") (class "Default")
      (node (ref "IC5") (pin "10") (pinfunction "OE_10") (pintype "input"))
      (node (ref "OUT5-6") (pin "5") (pinfunction "5_5") (pintype "passive"))
      (node (ref "RN4") (pin "7") (pinfunction "7_7") (pintype "passive"))
    )
    (net (code "64") (name "Net-(IC5D-I)") (class "Default")
      (node (ref "IC5") (pin "12") (pinfunction "I_12") (pintype "input"))
      (node (ref "OUT5-6") (pin "8") (pinfunction "8_8") (pintype "passive"))
    )
    (net (code "65") (name "Net-(IC5D-OE)") (class "Default")
      (node (ref "IC5") (pin "13") (pinfunction "OE_13") (pintype "input"))
      (node (ref "OUT5-6") (pin "7") (pinfunction "7_7") (pintype "passive"))
      (node (ref "RN4") (pin "6") (pinfunction "6_6") (pintype "passive"))
    )
    (net (code "66") (name "Net-(IC6A-I)") (class "Default")
      (node (ref "IC6") (pin "2") (pinfunction "I_2") (pintype "input"))
      (node (ref "OUT5-6") (pin "10") (pinfunction "10_10") (pintype "passive"))
    )
    (net (code "67") (name "Net-(IC6A-OE)") (class "Default")
      (node (ref "IC6") (pin "1") (pinfunction "OE_1") (pintype "input"))
      (node (ref "OUT5-6") (pin "9") (pinfunction "9_9") (pintype "passive"))
      (node (ref "RN4") (pin "5") (pinfunction "5_5") (pintype "passive"))
    )
    (net (code "68") (name "Net-(IC6B-I)") (class "Default")
      (node (ref "IC6") (pin "5") (pinfunction "I_5") (pintype "input"))
      (node (ref "OUT5-6") (pin "12") (pinfunction "12_12") (pintype "passive"))
    )
    (net (code "69") (name "Net-(IC6B-OE)") (class "Default")
      (node (ref "IC6") (pin "4") (pinfunction "OE_4") (pintype "input"))
      (node (ref "OUT5-6") (pin "11") (pinfunction "11_11") (pintype "passive"))
      (node (ref "RN4") (pin "4") (pinfunction "4_4") (pintype "passive"))
    )
    (net (code "70") (name "Net-(IC6C-I)") (class "Default")
      (node (ref "IC6") (pin "9") (pinfunction "I_9") (pintype "input"))
      (node (ref "OUT5-6") (pin "14") (pinfunction "14_14") (pintype "passive"))
    )
    (net (code "71") (name "Net-(IC6C-OE)") (class "Default")
      (node (ref "IC6") (pin "10") (pinfunction "OE_10") (pintype "input"))
      (node (ref "OUT5-6") (pin "13") (pinfunction "13_13") (pintype "passive"))
      (node (ref "RN4") (pin "3") (pinfunction "3_3") (pintype "passive"))
    )
    (net (code "72") (name "Net-(IC6D-I)") (class "Default")
      (node (ref "IC6") (pin "12") (pinfunction "I_12") (pintype "input"))
      (node (ref "OUT5-6") (pin "16") (pinfunction "16_16") (pintype "passive"))
    )
    (net (code "73") (name "Net-(IC6D-OE)") (class "Default")
      (node (ref "IC6") (pin "13") (pinfunction "OE_13") (pintype "input"))
      (node (ref "OUT5-6") (pin "15") (pinfunction "15_15") (pintype "passive"))
      (node (ref "RN4") (pin "2") (pinfunction "2_2") (pintype "passive"))
    )
    (net (code "74") (name "Net-(IC7A-I)") (class "Default")
      (node (ref "IC7") (pin "2") (pinfunction "I_2") (pintype "input"))
      (node (ref "OUT7-8") (pin "2") (pinfunction "2_2") (pintype "passive"))
    )
    (net (code "75") (name "Net-(IC7A-OE)") (class "Default")
      (node (ref "IC7") (pin "1") (pinfunction "OE_1") (pintype "input"))
      (node (ref "OUT7-8") (pin "1") (pinfunction "1_1") (pintype "passive"))
      (node (ref "RN2") (pin "9") (pinfunction "9_9") (pintype "passive"))
    )
    (net (code "76") (name "Net-(IC7B-I)") (class "Default")
      (node (ref "IC7") (pin "5") (pinfunction "I_5") (pintype "input"))
      (node (ref "OUT7-8") (pin "4") (pinfunction "4_4") (pintype "passive"))
    )
    (net (code "77") (name "Net-(IC7B-OE)") (class "Default")
      (node (ref "IC7") (pin "4") (pinfunction "OE_4") (pintype "input"))
      (node (ref "OUT7-8") (pin "3") (pinfunction "3_3") (pintype "passive"))
      (node (ref "RN2") (pin "8") (pinfunction "8_8") (pintype "passive"))
    )
    (net (code "78") (name "Net-(IC7C-I)") (class "Default")
      (node (ref "IC7") (pin "9") (pinfunction "I_9") (pintype "input"))
      (node (ref "OUT7-8") (pin "6") (pinfunction "6_6") (pintype "passive"))
    )
    (net (code "79") (name "Net-(IC7C-OE)") (class "Default")
      (node (ref "IC7") (pin "10") (pinfunction "OE_10") (pintype "input"))
      (node (ref "OUT7-8") (pin "5") (pinfunction "5_5") (pintype "passive"))
      (node (ref "RN2") (pin "7") (pinfunction "7_7") (pintype "passive"))
    )
    (net (code "80") (name "Net-(IC7D-I)") (class "Default")
      (node (ref "IC7") (pin "12") (pinfunction "I_12") (pintype "input"))
      (node (ref "OUT7-8") (pin "8") (pinfunction "8_8") (pintype "passive"))
    )
    (net (code "81") (name "Net-(IC7D-OE)") (class "Default")
      (node (ref "IC7") (pin "13") (pinfunction "OE_13") (pintype "input"))
      (node (ref "OUT7-8") (pin "7") (pinfunction "7_7") (pintype "passive"))
      (node (ref "RN2") (pin "6") (pinfunction "6_6") (pintype "passive"))
    )
    (net (code "82") (name "Net-(IC8A-I)") (class "Default")
      (node (ref "IC8") (pin "2") (pinfunction "I_2") (pintype "input"))
      (node (ref "OUT7-8") (pin "10") (pinfunction "10_10") (pintype "passive"))
    )
    (net (code "83") (name "Net-(IC8A-OE)") (class "Default")
      (node (ref "IC8") (pin "1") (pinfunction "OE_1") (pintype "input"))
      (node (ref "OUT7-8") (pin "9") (pinfunction "9_9") (pintype "passive"))
      (node (ref "RN2") (pin "5") (pinfunction "5_5") (pintype "passive"))
    )
    (net (code "84") (name "Net-(IC8B-I)") (class "Default")
      (node (ref "IC8") (pin "5") (pinfunction "I_5") (pintype "input"))
      (node (ref "OUT7-8") (pin "12") (pinfunction "12_12") (pintype "passive"))
    )
    (net (code "85") (name "Net-(IC8B-OE)") (class "Default")
      (node (ref "IC8") (pin "4") (pinfunction "OE_4") (pintype "input"))
      (node (ref "OUT7-8") (pin "11") (pinfunction "11_11") (pintype "passive"))
      (node (ref "RN2") (pin "4") (pinfunction "4_4") (pintype "passive"))
    )
    (net (code "86") (name "Net-(IC8C-I)") (class "Default")
      (node (ref "IC8") (pin "9") (pinfunction "I_9") (pintype "input"))
      (node (ref "OUT7-8") (pin "14") (pinfunction "14_14") (pintype "passive"))
    )
    (net (code "87") (name "Net-(IC8C-OE)") (class "Default")
      (node (ref "IC8") (pin "10") (pinfunction "OE_10") (pintype "input"))
      (node (ref "OUT7-8") (pin "13") (pinfunction "13_13") (pintype "passive"))
      (node (ref "RN2") (pin "3") (pinfunction "3_3") (pintype "passive"))
    )
    (net (code "88") (name "Net-(IC8D-I)") (class "Default")
      (node (ref "IC8") (pin "12") (pinfunction "I_12") (pintype "input"))
      (node (ref "OUT7-8") (pin "16") (pinfunction "16_16") (pintype "passive"))
    )
    (net (code "89") (name "Net-(IC8D-OE)") (class "Default")
      (node (ref "IC8") (pin "13") (pinfunction "OE_13") (pintype "input"))
      (node (ref "OUT7-8") (pin "15") (pinfunction "15_15") (pintype "passive"))
      (node (ref "RN2") (pin "2") (pinfunction "2_2") (pintype "passive"))
    )
    (net (code "90") (name "Net-(IC9B-I1)") (class "Default")
      (node (ref "!IO9") (pin "1") (pinfunction "1_1") (pintype "passive"))
      (node (ref "IC9") (pin "4") (pinfunction "I1_4") (pintype "input"))
    )
    (net (code "91") (name "Net-(IC9C-I1)") (class "Default")
      (node (ref "!IO8") (pin "1") (pinfunction "1_1") (pintype "passive"))
      (node (ref "IC9") (pin "10") (pinfunction "I1_10") (pintype "input"))
    )
    (net (code "92") (name "Net-(IC9C-I2)") (class "Default")
      (node (ref "C1") (pin "1") (pinfunction "1_1") (pintype "passive"))
      (node (ref "IC9") (pin "11") (pinfunction "I2_11") (pintype "input"))
      (node (ref "R1") (pin "1") (pinfunction "1_1") (pintype "passive"))
    )
    (net (code "93") (name "OA1") (class "Default")
      (node (ref "A1-K1") (pin "18") (pinfunction "18_18") (pintype "passive"))
      (node (ref "IC1") (pin "3") (pinfunction "O_3") (pintype "tri_state"))
      (node (ref "IN1-2") (pin "1") (pinfunction "1_1") (pintype "passive"))
      (node (ref "JP1") (pin "1") (pinfunction "1_1") (pintype "passive"))
    )
    (net (code "94") (name "OB1") (class "Default")
      (node (ref "A1-K1") (pin "17") (pinfunction "17_17") (pintype "passive"))
      (node (ref "IC1") (pin "6") (pinfunction "O_6") (pintype "tri_state"))
      (node (ref "IN1-2") (pin "3") (pinfunction "3_3") (pintype "passive"))
      (node (ref "JP1") (pin "2") (pinfunction "2_2") (pintype "passive"))
    )
    (net (code "95") (name "OB2") (class "Default")
      (node (ref "A2-K2") (pin "17") (pinfunction "17_17") (pintype "passive"))
      (node (ref "JP2") (pin "2") (pinfunction "2_2") (pintype "passive"))
    )
    (net (code "96") (name "OC") (class "Default")
      (node (ref "IC9") (pin "5") (pinfunction "I2_5") (pintype "input"))
      (node (ref "IC9") (pin "8") (pinfunction "O_8") (pintype "output"))
      (node (ref "IN5-6") (pin "1") (pinfunction "1_1") (pintype "passive"))
      (node (ref "OC") (pin "1") (pinfunction "1_1") (pintype "passive"))
    )
    (net (code "97") (name "OC1") (class "Default")
      (node (ref "A1-K1") (pin "16") (pinfunction "16_16") (pintype "passive"))
      (node (ref "IC1") (pin "8") (pinfunction "O_8") (pintype "tri_state"))
      (node (ref "IN1-2") (pin "5") (pinfunction "5_5") (pintype "passive"))
      (node (ref "JP1") (pin "3") (pinfunction "3_3") (pintype "passive"))
    )
    (net (code "98") (name "OD1") (class "Default")
      (node (ref "A1-K1") (pin "15") (pinfunction "15_15") (pintype "passive"))
      (node (ref "IC1") (pin "11") (pinfunction "O_11") (pintype "tri_state"))
      (node (ref "IN1-2") (pin "7") (pinfunction "7_7") (pintype "passive"))
      (node (ref "JP1") (pin "4") (pinfunction "4_4") (pintype "passive"))
    )
    (net (code "99") (name "OD2") (class "Default")
      (node (ref "A2-K2") (pin "15") (pinfunction "15_15") (pintype "passive"))
      (node (ref "IC5") (pin "6") (pinfunction "O_6") (pintype "tri_state"))
      (node (ref "IN3-4") (pin "3") (pinfunction "3_3") (pintype "passive"))
      (node (ref "JP2") (pin "4") (pinfunction "4_4") (pintype "passive"))
    )
    (net (code "100") (name "OE1") (class "Default")
      (node (ref "A1-K1") (pin "14") (pinfunction "14_14") (pintype "passive"))
      (node (ref "IC2") (pin "3") (pinfunction "O_3") (pintype "tri_state"))
      (node (ref "IN1-2") (pin "2") (pinfunction "2_2") (pintype "passive"))
      (node (ref "JP1") (pin "5") (pinfunction "5_5") (pintype "passive"))
    )
    (net (code "101") (name "OE2") (class "Default")
      (node (ref "A2-K2") (pin "14") (pinfunction "14_14") (pintype "passive"))
      (node (ref "IC5") (pin "8") (pinfunction "O_8") (pintype "tri_state"))
      (node (ref "IN3-4") (pin "5") (pinfunction "5_5") (pintype "passive"))
      (node (ref "JP2") (pin "5") (pinfunction "5_5") (pintype "passive"))
    )
    (net (code "102") (name "OF1") (class "Default")
      (node (ref "A1-K1") (pin "13") (pinfunction "13_13") (pintype "passive"))
      (node (ref "IC2") (pin "6") (pinfunction "O_6") (pintype "tri_state"))
      (node (ref "IN1-2") (pin "4") (pinfunction "4_4") (pintype "passive"))
      (node (ref "JP1") (pin "6") (pinfunction "6_6") (pintype "passive"))
    )
    (net (code "103") (name "OF2") (class "Default")
      (node (ref "A2-K2") (pin "13") (pinfunction "13_13") (pintype "passive"))
      (node (ref "IC5") (pin "11") (pinfunction "O_11") (pintype "tri_state"))
      (node (ref "IN3-4") (pin "7") (pinfunction "7_7") (pintype "passive"))
      (node (ref "JP2") (pin "6") (pinfunction "6_6") (pintype "passive"))
    )
    (net (code "104") (name "OH1") (class "Default")
      (node (ref "A1-K1") (pin "12") (pinfunction "12_12") (pintype "passive"))
      (node (ref "IC2") (pin "8") (pinfunction "O_8") (pintype "tri_state"))
      (node (ref "IN1-2") (pin "6") (pinfunction "6_6") (pintype "passive"))
      (node (ref "JP1") (pin "7") (pinfunction "7_7") (pintype "passive"))
    )
    (net (code "105") (name "OH2") (class "Default")
      (node (ref "A2-K2") (pin "12") (pinfunction "12_12") (pintype "passive"))
      (node (ref "IC6") (pin "3") (pinfunction "O_3") (pintype "tri_state"))
      (node (ref "IN3-4") (pin "2") (pinfunction "2_2") (pintype "passive"))
      (node (ref "JP2") (pin "7") (pinfunction "7_7") (pintype "passive"))
    )
    (net (code "106") (name "OJ1") (class "Default")
      (node (ref "A1-K1") (pin "11") (pinfunction "11_11") (pintype "passive"))
      (node (ref "IC2") (pin "11") (pinfunction "O_11") (pintype "tri_state"))
      (node (ref "IN1-2") (pin "8") (pinfunction "8_8") (pintype "passive"))
      (node (ref "JP1") (pin "8") (pinfunction "8_8") (pintype "passive"))
    )
    (net (code "107") (name "OJ2") (class "Default")
      (node (ref "A2-K2") (pin "11") (pinfunction "11_11") (pintype "passive"))
      (node (ref "IC6") (pin "6") (pinfunction "O_6") (pintype "tri_state"))
      (node (ref "IN3-4") (pin "4") (pinfunction "4_4") (pintype "passive"))
      (node (ref "JP2") (pin "8") (pinfunction "8_8") (pintype "passive"))
    )
    (net (code "108") (name "OK1") (class "Default")
      (node (ref "A1-K1") (pin "10") (pinfunction "10_10") (pintype "passive"))
      (node (ref "IC3") (pin "3") (pinfunction "O_3") (pintype "tri_state"))
      (node (ref "IN1-2") (pin "9") (pinfunction "9_9") (pintype "passive"))
      (node (ref "JP1") (pin "9") (pinfunction "9_9") (pintype "passive"))
    )
    (net (code "109") (name "OK2") (class "Default")
      (node (ref "A2-K2") (pin "10") (pinfunction "10_10") (pintype "passive"))
      (node (ref "IC6") (pin "8") (pinfunction "O_8") (pintype "tri_state"))
      (node (ref "IN3-4") (pin "6") (pinfunction "6_6") (pintype "passive"))
      (node (ref "JP2") (pin "9") (pinfunction "9_9") (pintype "passive"))
    )
    (net (code "110") (name "OL1") (class "Default")
      (node (ref "IC3") (pin "6") (pinfunction "O_6") (pintype "tri_state"))
      (node (ref "IN1-2") (pin "11") (pinfunction "11_11") (pintype "passive"))
      (node (ref "JP1") (pin "10") (pinfunction "10_10") (pintype "passive"))
      (node (ref "L1-V1") (pin "18") (pinfunction "18_18") (pintype "passive"))
    )
    (net (code "111") (name "OL2") (class "Default")
      (node (ref "IC6") (pin "11") (pinfunction "O_11") (pintype "tri_state"))
      (node (ref "IN3-4") (pin "8") (pinfunction "8_8") (pintype "passive"))
      (node (ref "JP2") (pin "10") (pinfunction "10_10") (pintype "passive"))
      (node (ref "L2-V2") (pin "18") (pinfunction "18_18") (pintype "passive"))
    )
    (net (code "112") (name "OM1") (class "Default")
      (node (ref "IC3") (pin "8") (pinfunction "O_8") (pintype "tri_state"))
      (node (ref "IN1-2") (pin "13") (pinfunction "13_13") (pintype "passive"))
      (node (ref "JP1") (pin "11") (pinfunction "11_11") (pintype "passive"))
      (node (ref "L1-V1") (pin "17") (pinfunction "17_17") (pintype "passive"))
    )
    (net (code "113") (name "OM2") (class "Default")
      (node (ref "IC7") (pin "3") (pinfunction "O_3") (pintype "tri_state"))
      (node (ref "IN3-4") (pin "9") (pinfunction "9_9") (pintype "passive"))
      (node (ref "JP2") (pin "11") (pinfunction "11_11") (pintype "passive"))
      (node (ref "L2-V2") (pin "17") (pinfunction "17_17") (pintype "passive"))
    )
    (net (code "114") (name "ON1") (class "Default")
      (node (ref "IC3") (pin "11") (pinfunction "O_11") (pintype "tri_state"))
      (node (ref "IN1-2") (pin "15") (pinfunction "15_15") (pintype "passive"))
      (node (ref "JP1") (pin "12") (pinfunction "12_12") (pintype "passive"))
      (node (ref "L1-V1") (pin "16") (pinfunction "16_16") (pintype "passive"))
    )
    (net (code "115") (name "ON2") (class "Default")
      (node (ref "IC7") (pin "6") (pinfunction "O_6") (pintype "tri_state"))
      (node (ref "IN3-4") (pin "11") (pinfunction "11_11") (pintype "passive"))
      (node (ref "JP2") (pin "12") (pinfunction "12_12") (pintype "passive"))
      (node (ref "L2-V2") (pin "16") (pinfunction "16_16") (pintype "passive"))
    )
    (net (code "116") (name "OP1") (class "Default")
      (node (ref "IC4") (pin "3") (pinfunction "O_3") (pintype "tri_state"))
      (node (ref "IN1-2") (pin "10") (pinfunction "10_10") (pintype "passive"))
      (node (ref "JP1") (pin "13") (pinfunction "13_13") (pintype "passive"))
      (node (ref "L1-V1") (pin "15") (pinfunction "15_15") (pintype "passive"))
    )
    (net (code "117") (name "OP2") (class "Default")
      (node (ref "IC7") (pin "8") (pinfunction "O_8") (pintype "tri_state"))
      (node (ref "IN3-4") (pin "13") (pinfunction "13_13") (pintype "passive"))
      (node (ref "JP2") (pin "13") (pinfunction "13_13") (pintype "passive"))
      (node (ref "L2-V2") (pin "15") (pinfunction "15_15") (pintype "passive"))
    )
    (net (code "118") (name "OR1") (class "Default")
      (node (ref "IC4") (pin "6") (pinfunction "O_6") (pintype "tri_state"))
      (node (ref "IN1-2") (pin "12") (pinfunction "12_12") (pintype "passive"))
      (node (ref "JP1") (pin "14") (pinfunction "14_14") (pintype "passive"))
      (node (ref "L1-V1") (pin "14") (pinfunction "14_14") (pintype "passive"))
    )
    (net (code "119") (name "OR2") (class "Default")
      (node (ref "IC7") (pin "11") (pinfunction "O_11") (pintype "tri_state"))
      (node (ref "IN3-4") (pin "15") (pinfunction "15_15") (pintype "passive"))
      (node (ref "JP2") (pin "14") (pinfunction "14_14") (pintype "passive"))
      (node (ref "L2-V2") (pin "14") (pinfunction "14_14") (pintype "passive"))
    )
    (net (code "120") (name "OS1") (class "Default")
      (node (ref "IC4") (pin "8") (pinfunction "O_8") (pintype "tri_state"))
      (node (ref "IN1-2") (pin "14") (pinfunction "14_14") (pintype "passive"))
      (node (ref "JP1") (pin "15") (pinfunction "15_15") (pintype "passive"))
      (node (ref "L1-V1") (pin "13") (pinfunction "13_13") (pintype "passive"))
    )
    (net (code "121") (name "OS2") (class "Default")
      (node (ref "IC8") (pin "3") (pinfunction "O_3") (pintype "tri_state"))
      (node (ref "IN3-4") (pin "10") (pinfunction "10_10") (pintype "passive"))
      (node (ref "JP2") (pin "15") (pinfunction "15_15") (pintype "passive"))
      (node (ref "L2-V2") (pin "13") (pinfunction "13_13") (pintype "passive"))
    )
    (net (code "122") (name "OT2") (class "Default")
      (node (ref "IC8") (pin "6") (pinfunction "O_6") (pintype "tri_state"))
      (node (ref "IN3-4") (pin "12") (pinfunction "12_12") (pintype "passive"))
      (node (ref "JP2") (pin "16") (pinfunction "16_16") (pintype "passive"))
      (node (ref "L2-V2") (pin "12") (pinfunction "12_12") (pintype "passive"))
    )
    (net (code "123") (name "OU1") (class "Default")
      (node (ref "IC4") (pin "11") (pinfunction "O_11") (pintype "tri_state"))
      (node (ref "IN1-2") (pin "16") (pinfunction "16_16") (pintype "passive"))
      (node (ref "JP1") (pin "17") (pinfunction "17_17") (pintype "passive"))
      (node (ref "L1-V1") (pin "11") (pinfunction "11_11") (pintype "passive"))
    )
    (net (code "124") (name "OU2") (class "Default")
      (node (ref "IC8") (pin "8") (pinfunction "O_8") (pintype "tri_state"))
      (node (ref "IN3-4") (pin "14") (pinfunction "14_14") (pintype "passive"))
      (node (ref "JP2") (pin "17") (pinfunction "17_17") (pintype "passive"))
      (node (ref "L2-V2") (pin "11") (pinfunction "11_11") (pintype "passive"))
    )
    (net (code "125") (name "OV1") (class "Default")
      (node (ref "IC5") (pin "3") (pinfunction "O_3") (pintype "tri_state"))
      (node (ref "IN3-4") (pin "1") (pinfunction "1_1") (pintype "passive"))
      (node (ref "JP1") (pin "18") (pinfunction "18_18") (pintype "passive"))
      (node (ref "L1-V1") (pin "10") (pinfunction "10_10") (pintype "passive"))
    )
    (net (code "126") (name "OV2") (class "Default")
      (node (ref "IC8") (pin "11") (pinfunction "O_11") (pintype "tri_state"))
      (node (ref "IN3-4") (pin "16") (pinfunction "16_16") (pintype "passive"))
      (node (ref "JP2") (pin "18") (pinfunction "18_18") (pintype "passive"))
      (node (ref "L2-V2") (pin "10") (pinfunction "10_10") (pintype "passive"))
    )
    (net (code "127") (name "P1") (class "Default")
      (node (ref "JP3") (pin "13") (pinfunction "13_13") (pintype "passive"))
      (node (ref "L1-V1") (pin "4") (pinfunction "4_4") (pintype "passive"))
      (node (ref "SIDE1") (pin "30") (pinfunction "30_30") (pintype "passive"))
    )
    (net (code "128") (name "P2") (class "Default")
      (node (ref "JP4") (pin "13") (pinfunction "13_13") (pintype "passive"))
      (node (ref "L2-V2") (pin "4") (pinfunction "4_4") (pintype "passive"))
      (node (ref "SIDE2") (pin "24") (pinfunction "24_24") (pintype "passive"))
    )
    (net (code "129") (name "R1") (class "Default")
      (node (ref "JP3") (pin "14") (pinfunction "14_14") (pintype "passive"))
      (node (ref "L1-V1") (pin "5") (pinfunction "5_5") (pintype "passive"))
      (node (ref "SIDE1") (pin "26") (pinfunction "26_26") (pintype "passive"))
    )
    (net (code "130") (name "R2") (class "Default")
      (node (ref "JP4") (pin "14") (pinfunction "14_14") (pintype "passive"))
      (node (ref "L2-V2") (pin "5") (pinfunction "5_5") (pintype "passive"))
      (node (ref "SIDE2") (pin "26") (pinfunction "26_26") (pintype "passive"))
    )
    (net (code "131") (name "S1") (class "Default")
      (node (ref "JP3") (pin "15") (pinfunction "15_15") (pintype "passive"))
      (node (ref "L1-V1") (pin "6") (pinfunction "6_6") (pintype "passive"))
      (node (ref "SIDE1") (pin "32") (pinfunction "32_32") (pintype "passive"))
    )
    (net (code "132") (name "S2") (class "Default")
      (node (ref "JP4") (pin "15") (pinfunction "15_15") (pintype "passive"))
      (node (ref "L2-V2") (pin "6") (pinfunction "6_6") (pintype "passive"))
      (node (ref "SIDE2") (pin "28") (pinfunction "28_28") (pintype "passive"))
    )
    (net (code "133") (name "T1") (class "Default")
      (node (ref "JP3") (pin "16") (pinfunction "16_16") (pintype "passive"))
      (node (ref "L1-V1") (pin "7") (pinfunction "7_7") (pintype "passive"))
      (node (ref "SIDE1") (pin "34") (pinfunction "34_34") (pintype "passive"))
    )
    (net (code "134") (name "T2") (class "Default")
      (node (ref "JP4") (pin "16") (pinfunction "16_16") (pintype "passive"))
      (node (ref "L2-V2") (pin "7") (pinfunction "7_7") (pintype "passive"))
      (node (ref "SIDE2") (pin "30") (pinfunction "30_30") (pintype "passive"))
    )
    (net (code "135") (name "U1") (class "Default")
      (node (ref "JP3") (pin "17") (pinfunction "17_17") (pintype "passive"))
      (node (ref "L1-V1") (pin "8") (pinfunction "8_8") (pintype "passive"))
      (node (ref "SIDE1") (pin "4") (pinfunction "4_4") (pintype "passive"))
    )
    (net (code "136") (name "U2") (class "Default")
      (node (ref "JP4") (pin "17") (pinfunction "17_17") (pintype "passive"))
      (node (ref "L2-V2") (pin "8") (pinfunction "8_8") (pintype "passive"))
      (node (ref "SIDE2") (pin "34") (pinfunction "34_34") (pintype "passive"))
    )
    (net (code "137") (name "V1") (class "Default")
      (node (ref "JP3") (pin "18") (pinfunction "18_18") (pintype "passive"))
      (node (ref "L1-V1") (pin "9") (pinfunction "9_9") (pintype "passive"))
      (node (ref "SIDE1") (pin "2") (pinfunction "2_2") (pintype "passive"))
    )
    (net (code "138") (name "V2") (class "Default")
      (node (ref "JP4") (pin "18") (pinfunction "18_18") (pintype "passive"))
      (node (ref "L2-V2") (pin "9") (pinfunction "9_9") (pintype "passive"))
      (node (ref "SIDE2") (pin "32") (pinfunction "32_32") (pintype "passive"))
    )
    (net (code "139") (name "VCC") (class "Default")
      (node (ref "A2-K2") (pin "18") (pinfunction "18_18") (pintype "passive"))
      (node (ref "BYP1") (pin "1") (pinfunction "1_1") (pintype "passive"))
      (node (ref "BYP10") (pin "1") (pinfunction "1_1") (pintype "passive"))
      (node (ref "BYP2") (pin "1") (pinfunction "1_1") (pintype "passive"))
      (node (ref "BYP3") (pin "1") (pinfunction "1_1") (pintype "passive"))
      (node (ref "BYP4") (pin "1") (pinfunction "1_1") (pintype "passive"))
      (node (ref "BYP5") (pin "1") (pinfunction "1_1") (pintype "passive"))
      (node (ref "BYP6") (pin "1") (pinfunction "1_1") (pintype "passive"))
      (node (ref "BYP7") (pin "1") (pinfunction "1_1") (pintype "passive"))
      (node (ref "BYP8") (pin "1") (pinfunction "1_1") (pintype "passive"))
      (node (ref "BYP9") (pin "1") (pinfunction "1_1") (pintype "passive"))
      (node (ref "IC9") (pin "1") (pinfunction "I0_1") (pintype "input"))
      (node (ref "IC9") (pin "13") (pinfunction "I2_13") (pintype "input"))
      (node (ref "IC9") (pin "2") (pinfunction "I1_2") (pintype "input"))
      (node (ref "IC9") (pin "3") (pinfunction "I0_3") (pintype "input"))
      (node (ref "JP2") (pin "1") (pinfunction "1_1") (pintype "passive"))
      (node (ref "POWER") (pin "2") (pinfunction "2_2") (pintype "passive"))
      (node (ref "POWER2") (pin "2") (pinfunction "2_2") (pintype "passive"))
      (node (ref "RN1") (pin "1") (pinfunction "1_1") (pintype "passive"))
      (node (ref "RN2") (pin "1") (pinfunction "1_1") (pintype "passive"))
      (node (ref "RN3") (pin "1") (pinfunction "1_1") (pintype "passive"))
      (node (ref "RN4") (pin "1") (pinfunction "1_1") (pintype "passive"))
    )
    (net (code "140") (name "unconnected-(IC9A-O-Pad12)") (class "Default")
      (node (ref "IC9") (pin "12") (pinfunction "O_12") (pintype "output"))
    )
    (net (code "141") (name "unconnected-(IN5-6-Pad2)") (class "Default")
      (node (ref "IN5-6") (pin "2") (pinfunction "2_2") (pintype "passive"))
    )
    (net (code "142") (name "unconnected-(IN5-6-Pad3)") (class "Default")
      (node (ref "IN5-6") (pin "3") (pinfunction "3_3") (pintype "passive"))
    )
    (net (code "143") (name "unconnected-(IN5-6-Pad4)") (class "Default")
      (node (ref "IN5-6") (pin "4") (pinfunction "4_4") (pintype "passive"))
    )
    (net (code "144") (name "unconnected-(IN5-6-Pad5)") (class "Default")
      (node (ref "IN5-6") (pin "5") (pinfunction "5_5") (pintype "passive"))
    )
    (net (code "145") (name "unconnected-(IN5-6-Pad6)") (class "Default")
      (node (ref "IN5-6") (pin "6") (pinfunction "6_6") (pintype "passive"))
    )
    (net (code "146") (name "unconnected-(IN5-6-Pad7)") (class "Default")
      (node (ref "IN5-6") (pin "7") (pinfunction "7_7") (pintype "passive"))
    )
    (net (code "147") (name "unconnected-(IN5-6-Pad8)") (class "Default")
      (node (ref "IN5-6") (pin "8") (pinfunction "8_8") (pintype "passive"))
    )
    (net (code "148") (name "unconnected-(IN5-6-Pad9)") (class "Default")
      (node (ref "IN5-6") (pin "9") (pinfunction "9_9") (pintype "passive"))
    )
    (net (code "149") (name "unconnected-(IN5-6-Pad10)") (class "Default")
      (node (ref "IN5-6") (pin "10") (pinfunction "10_10") (pintype "passive"))
    )
    (net (code "150") (name "unconnected-(IN5-6-Pad11)") (class "Default")
      (node (ref "IN5-6") (pin "11") (pinfunction "11_11") (pintype "passive"))
    )
    (net (code "151") (name "unconnected-(IN5-6-Pad12)") (class "Default")
      (node (ref "IN5-6") (pin "12") (pinfunction "12_12") (pintype "passive"))
    )
    (net (code "152") (name "unconnected-(IN5-6-Pad13)") (class "Default")
      (node (ref "IN5-6") (pin "13") (pinfunction "13_13") (pintype "passive"))
    )
    (net (code "153") (name "unconnected-(IN5-6-Pad14)") (class "Default")
      (node (ref "IN5-6") (pin "14") (pinfunction "14_14") (pintype "passive"))
    )
    (net (code "154") (name "unconnected-(IN5-6-Pad15)") (class "Default")
      (node (ref "IN5-6") (pin "15") (pinfunction "15_15") (pintype "passive"))
    )
    (net (code "155") (name "unconnected-(IN5-6-Pad16)") (class "Default")
      (node (ref "IN5-6") (pin "16") (pinfunction "16_16") (pintype "passive"))
    )
    (net (code "156") (name "unconnected-(RN1-Pad10)") (class "Default")
      (node (ref "RN1") (pin "10") (pinfunction "10_10") (pintype "passive"))
    )
    (net (code "157") (name "unconnected-(RN1-Pad11)") (class "Default")
      (node (ref "RN1") (pin "11") (pinfunction "11_11") (pintype "passive"))
    )
    (net (code "158") (name "unconnected-(RN2-Pad10)") (class "Default")
      (node (ref "RN2") (pin "10") (pinfunction "10_10") (pintype "passive"))
    )
    (net (code "159") (name "unconnected-(RN2-Pad11)") (class "Default")
      (node (ref "RN2") (pin "11") (pinfunction "11_11") (pintype "passive"))
    )
    (net (code "160") (name "unconnected-(RN3-Pad10)") (class "Default")
      (node (ref "RN3") (pin "10") (pinfunction "10_10") (pintype "passive"))
    )
    (net (code "161") (name "unconnected-(RN3-Pad11)") (class "Default")
      (node (ref "RN3") (pin "11") (pinfunction "11_11") (pintype "passive"))
    )
    (net (code "162") (name "unconnected-(RN4-Pad10)") (class "Default")
      (node (ref "RN4") (pin "10") (pinfunction "10_10") (pintype "passive"))
    )
    (net (code "163") (name "unconnected-(RN4-Pad11)") (class "Default")
      (node (ref "RN4") (pin "11") (pinfunction "11_11") (pintype "passive"))
    )
    (net (code "164") (name "~{MR}") (class "Default")
      (node (ref "!MR") (pin "1") (pinfunction "1_1") (pintype "passive"))
      (node (ref "IC9") (pin "6") (pinfunction "O_6") (pintype "output"))
      (node (ref "IC9") (pin "9") (pinfunction "I0_9") (pintype "input"))
    )
  )
)
